# RF1_12V.net
KiCad netlist of a schematic drawn in EAGLE
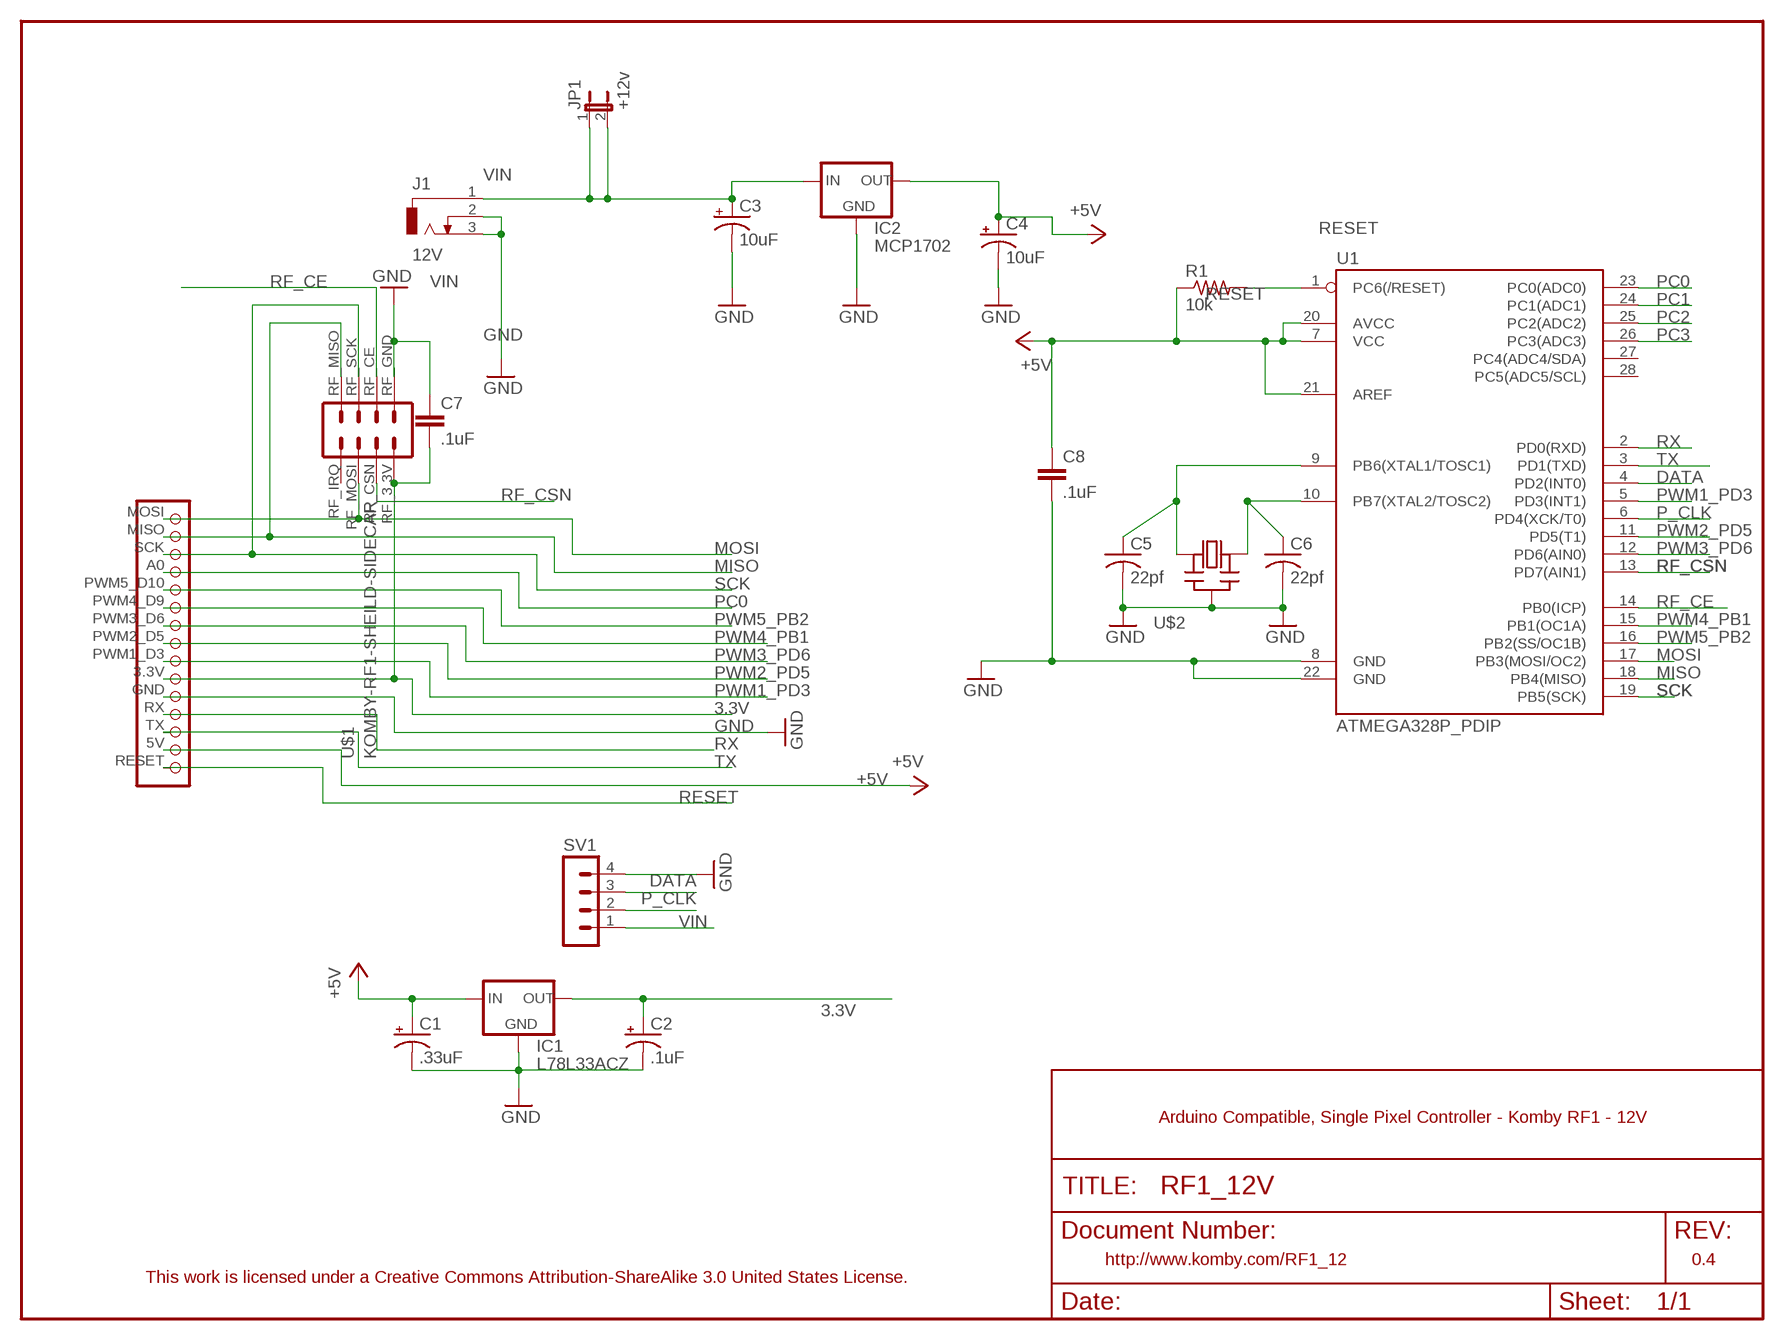
[diagram p0: schematic, sheet 1]

(export (version "E")
  (design (tool "Eeschema 10.0.6"))
  (components
    (comp (ref "C1")
      (value ".33uF")
      (footprint "eagle-import:E1,8-4")
      (libsource (lib "eagle-import") (part "CPOL-USE1.8-4"))
    )
    (comp (ref "C2")
      (value ".1uF")
      (footprint "eagle-import:E1,8-4")
      (libsource (lib "eagle-import") (part "CPOL-USE1.8-4"))
    )
    (comp (ref "C3")
      (value "10uF")
      (footprint "eagle-import:E1,8-4")
      (libsource (lib "eagle-import") (part "CPOL-USE1.8-4"))
    )
    (comp (ref "C4")
      (value "10uF")
      (footprint "eagle-import:E1,8-4")
      (libsource (lib "eagle-import") (part "CPOL-USE1.8-4"))
    )
    (comp (ref "C5")
      (value "22pf")
      (footprint "eagle-import:C0805")
      (libsource (lib "eagle-import") (part "C-USC0805"))
    )
    (comp (ref "C6")
      (value "22pf")
      (footprint "eagle-import:C0805")
      (libsource (lib "eagle-import") (part "C-USC0805"))
    )
    (comp (ref "C7")
      (value ".1uF")
      (footprint "eagle-import:C025-024X044")
      (libsource (lib "eagle-import") (part "C-EU025-024X044"))
    )
    (comp (ref "C8")
      (value ".1uF")
      (footprint "eagle-import:C025-024X044")
      (libsource (lib "eagle-import") (part "C-EU025-024X044"))
    )
    (comp (ref "IC1")
      (value "L78L33ACZ")
      (footprint "eagle-import:78LXX")
      (libsource (lib "eagle-import") (part "78LXX"))
    )
    (comp (ref "IC2")
      (value "MCP1702")
      (footprint "eagle-import:TO92")
      (libsource (lib "eagle-import") (part "MCP1700TRI"))
    )
    (comp (ref "J1")
      (value "12V")
      (footprint "eagle-import:DCJ0303")
      (libsource (lib "eagle-import") (part "DCJ0303"))
    )
    (comp (ref "JP1")
      (value "+12v")
      (footprint "eagle-import:JP1")
      (libsource (lib "eagle-import") (part "JP1E"))
    )
    (comp (ref "R1")
      (value "10k")
      (footprint "eagle-import:0207_7")
      (libsource (lib "eagle-import") (part "R-US_0207/7"))
    )
    (comp (ref "SV1")
      (value "MA04-1")
      (footprint "eagle-import:MA04-1")
      (libsource (lib "eagle-import") (part "MA04-1"))
    )
    (comp (ref "U$1")
      (value "KOMBY-RF1-SHEILD-SIDECAR")
      (footprint "eagle-import:KOMBY-RF1-SIDECAR")
      (libsource (lib "eagle-import") (part "KOMBY-RF1-SHEILD-SIDECAR"))
    )
    (comp (ref "U$2")
      (value "CERMOSCILL-THM")
      (footprint "eagle-import:CERM_OSC")
      (libsource (lib "eagle-import") (part "CERMOSCILL-THM"))
    )
    (comp (ref "U1")
      (value "ATMEGA328P_PDIP")
      (footprint "eagle-import:DIL28-3")
      (libsource (lib "eagle-import") (part "ATMEGA328P_PDIP"))
    )
  )
  (nets
    (net (code "1") (name "+5V") (class "Default")
      (node (ref "C1") (pin "+") (pinfunction "+_+") (pintype "passive"))
      (node (ref "C4") (pin "+") (pinfunction "+_+") (pintype "passive"))
      (node (ref "C8") (pin "1") (pinfunction "1_1") (pintype "passive"))
      (node (ref "IC1") (pin "IN") (pinfunction "IN_IN") (pintype "input"))
      (node (ref "IC2") (pin "3") (pinfunction "OUT_3") (pintype "passive"))
      (node (ref "R1") (pin "1") (pinfunction "1_1") (pintype "passive"))
      (node (ref "U$1") (pin "5V") (pinfunction "5V_5V") (pintype "passive"))
      (node (ref "U1") (pin "20") (pinfunction "AVCC_20") (pintype "bidirectional"))
      (node (ref "U1") (pin "21") (pinfunction "AREF_21") (pintype "bidirectional"))
      (node (ref "U1") (pin "7") (pinfunction "VCC_7") (pintype "bidirectional"))
    )
    (net (code "2") (name "/3.3V") (class "Default")
      (node (ref "C2") (pin "+") (pinfunction "+_+") (pintype "passive"))
      (node (ref "C7") (pin "2") (pinfunction "2_2") (pintype "passive"))
      (node (ref "IC1") (pin "OUT") (pinfunction "OUT_OUT") (pintype "passive"))
      (node (ref "U$1") (pin "3.3V") (pinfunction "3.3V_3.3V") (pintype "passive"))
      (node (ref "U$1") (pin "RF_3.3V") (pinfunction "RF_3.3V_RF_3.3V") (pintype "passive"))
    )
    (net (code "3") (name "/DATA") (class "Default")
      (node (ref "SV1") (pin "3") (pinfunction "3_3") (pintype "passive"))
      (node (ref "U1") (pin "4") (pinfunction "PD2(INT0)_4") (pintype "bidirectional"))
    )
    (net (code "4") (name "/MISO") (class "Default")
      (node (ref "U$1") (pin "MISO") (pinfunction "MISO_MISO") (pintype "passive"))
      (node (ref "U$1") (pin "RF_MISO") (pinfunction "RF_MISO_RF_MISO") (pintype "passive"))
      (node (ref "U1") (pin "18") (pinfunction "PB4(MISO)_18") (pintype "bidirectional"))
    )
    (net (code "5") (name "/MOSI") (class "Default")
      (node (ref "U$1") (pin "MOSI") (pinfunction "MOSI_MOSI") (pintype "passive"))
      (node (ref "U$1") (pin "RF_MOSI") (pinfunction "RF_MOSI_RF_MOSI") (pintype "passive"))
      (node (ref "U1") (pin "17") (pinfunction "PB3(MOSI/OC2)_17") (pintype "bidirectional"))
    )
    (net (code "6") (name "/PC0") (class "Default")
      (node (ref "U$1") (pin "A0") (pinfunction "PC0_A0") (pintype "passive"))
      (node (ref "U1") (pin "23") (pinfunction "PC0(ADC0)_23") (pintype "bidirectional"))
    )
    (net (code "7") (name "/PC1") (class "Default")
      (node (ref "U1") (pin "24") (pinfunction "PC1(ADC1)_24") (pintype "bidirectional"))
    )
    (net (code "8") (name "/PC2") (class "Default")
      (node (ref "U1") (pin "25") (pinfunction "PC2(ADC2)_25") (pintype "bidirectional"))
    )
    (net (code "9") (name "/PC3") (class "Default")
      (node (ref "U1") (pin "26") (pinfunction "PC3(ADC3)_26") (pintype "bidirectional"))
    )
    (net (code "10") (name "/PWM1_PD3") (class "Default")
      (node (ref "U$1") (pin "PWM1_D3") (pinfunction "PWM1_PWM1_D3") (pintype "passive"))
      (node (ref "U1") (pin "5") (pinfunction "PD3(INT1)_5") (pintype "bidirectional"))
    )
    (net (code "11") (name "/PWM2_PD5") (class "Default")
      (node (ref "U$1") (pin "PWM2_D5") (pinfunction "PWM2_PWM2_D5") (pintype "passive"))
      (node (ref "U1") (pin "11") (pinfunction "PD5(T1)_11") (pintype "bidirectional"))
    )
    (net (code "12") (name "/PWM3_PD6") (class "Default")
      (node (ref "U$1") (pin "PWM3_D6") (pinfunction "PWM3_PWM3_D6") (pintype "passive"))
      (node (ref "U1") (pin "12") (pinfunction "PD6(AIN0)_12") (pintype "bidirectional"))
    )
    (net (code "13") (name "/PWM4_PB1") (class "Default")
      (node (ref "U$1") (pin "PWM4_D9") (pinfunction "PWM4_PWM4_D9") (pintype "passive"))
      (node (ref "U1") (pin "15") (pinfunction "PB1(OC1A)_15") (pintype "bidirectional"))
    )
    (net (code "14") (name "/PWM5_PB2") (class "Default")
      (node (ref "U$1") (pin "PWM5_D10") (pinfunction "PWM5_PWM5_D10") (pintype "passive"))
      (node (ref "U1") (pin "16") (pinfunction "PB2(SS/OC1B)_16") (pintype "bidirectional"))
    )
    (net (code "15") (name "/P_CLK") (class "Default")
      (node (ref "SV1") (pin "2") (pinfunction "2_2") (pintype "passive"))
      (node (ref "U1") (pin "6") (pinfunction "PD4(XCK/T0)_6") (pintype "bidirectional"))
    )
    (net (code "16") (name "/RESET") (class "Default")
      (node (ref "R1") (pin "2") (pinfunction "2_2") (pintype "passive"))
      (node (ref "U$1") (pin "RESET") (pinfunction "RESET_RESET") (pintype "passive"))
      (node (ref "U1") (pin "1") (pinfunction "PC6(/RESET)_1") (pintype "bidirectional"))
    )
    (net (code "17") (name "/RF_CE") (class "Default")
      (node (ref "U$1") (pin "RF_CE") (pinfunction "RF_CE_RF_CE") (pintype "passive"))
      (node (ref "U1") (pin "14") (pinfunction "PB0(ICP)_14") (pintype "bidirectional"))
    )
    (net (code "18") (name "/RF_CSN") (class "Default")
      (node (ref "U$1") (pin "RF_CSN") (pinfunction "RF_CSN_RF_CSN") (pintype "passive"))
      (node (ref "U1") (pin "13") (pinfunction "PD7(AIN1)_13") (pintype "bidirectional"))
    )
    (net (code "19") (name "/RX") (class "Default")
      (node (ref "U$1") (pin "RX") (pinfunction "RX_RX") (pintype "passive"))
      (node (ref "U1") (pin "2") (pinfunction "PD0(RXD)_2") (pintype "bidirectional"))
    )
    (net (code "20") (name "/SCK") (class "Default")
      (node (ref "U$1") (pin "RF_SCK") (pinfunction "RF_SCK_RF_SCK") (pintype "passive"))
      (node (ref "U$1") (pin "SCK") (pinfunction "SCK_SCK") (pintype "passive"))
      (node (ref "U1") (pin "19") (pinfunction "PB5(SCK)_19") (pintype "bidirectional"))
    )
    (net (code "21") (name "/TX") (class "Default")
      (node (ref "U$1") (pin "TX") (pinfunction "TX_TX") (pintype "passive"))
      (node (ref "U1") (pin "3") (pinfunction "PD1(TXD)_3") (pintype "bidirectional"))
    )
    (net (code "22") (name "/VIN") (class "Default")
      (node (ref "C3") (pin "+") (pinfunction "+_+") (pintype "passive"))
      (node (ref "IC2") (pin "2") (pinfunction "IN_2") (pintype "input"))
      (node (ref "J1") (pin "1") (pinfunction "1_1") (pintype "passive"))
      (node (ref "JP1") (pin "1") (pinfunction "1_1") (pintype "passive"))
      (node (ref "JP1") (pin "2") (pinfunction "2_2") (pintype "passive"))
      (node (ref "SV1") (pin "1") (pinfunction "1_1") (pintype "passive"))
    )
    (net (code "23") (name "GND") (class "Default")
      (node (ref "C1") (pin "-") (pinfunction "-_-") (pintype "passive"))
      (node (ref "C2") (pin "-") (pinfunction "-_-") (pintype "passive"))
      (node (ref "C3") (pin "-") (pinfunction "-_-") (pintype "passive"))
      (node (ref "C4") (pin "-") (pinfunction "-_-") (pintype "passive"))
      (node (ref "C5") (pin "2") (pinfunction "2_2") (pintype "passive"))
      (node (ref "C6") (pin "2") (pinfunction "2_2") (pintype "passive"))
      (node (ref "C7") (pin "1") (pinfunction "1_1") (pintype "passive"))
      (node (ref "C8") (pin "2") (pinfunction "2_2") (pintype "passive"))
      (node (ref "IC1") (pin "GND") (pinfunction "GND_GND") (pintype "input"))
      (node (ref "IC2") (pin "1") (pinfunction "GND_1") (pintype "input"))
      (node (ref "J1") (pin "2") (pinfunction "2_2") (pintype "passive"))
      (node (ref "J1") (pin "3") (pinfunction "3_3") (pintype "passive"))
      (node (ref "SV1") (pin "4") (pinfunction "4_4") (pintype "passive"))
      (node (ref "U$1") (pin "GND") (pinfunction "GND_GND") (pintype "passive"))
      (node (ref "U$1") (pin "RF_GND") (pinfunction "RFGND_1_RF_GND") (pintype "passive"))
      (node (ref "U$2") (pin "P$2") (pinfunction "GND_P$2") (pintype "bidirectional"))
      (node (ref "U1") (pin "22") (pinfunction "GND_22") (pintype "bidirectional"))
      (node (ref "U1") (pin "8") (pinfunction "GND_8") (pintype "bidirectional"))
    )
    (net (code "24") (name "Net-(U$2-IN)") (class "Default")
      (node (ref "C5") (pin "1") (pinfunction "1_1") (pintype "passive"))
      (node (ref "U$2") (pin "P$1") (pinfunction "IN_P$1") (pintype "bidirectional"))
      (node (ref "U1") (pin "9") (pinfunction "PB6(XTAL1/TOSC1)_9") (pintype "bidirectional"))
    )
    (net (code "25") (name "Net-(U$2-OUT)") (class "Default")
      (node (ref "C6") (pin "1") (pinfunction "1_1") (pintype "passive"))
      (node (ref "U$2") (pin "P$3") (pinfunction "OUT_P$3") (pintype "bidirectional"))
      (node (ref "U1") (pin "10") (pinfunction "PB7(XTAL2/TOSC2)_10") (pintype "bidirectional"))
    )
    (net (code "26") (name "unconnected-(U$1-PadRF_IRQ)") (class "Default")
      (node (ref "U$1") (pin "RF_IRQ") (pinfunction "RF_IRQ_RF_IRQ") (pintype "passive"))
    )
    (net (code "27") (name "unconnected-(U1-PC4(ADC4{slash}SDA)-Pad27)") (class "Default")
      (node (ref "U1") (pin "27") (pinfunction "PC4(ADC4/SDA)_27") (pintype "bidirectional"))
    )
    (net (code "28") (name "unconnected-(U1-PC5(ADC5{slash}SCL)-Pad28)") (class "Default")
      (node (ref "U1") (pin "28") (pinfunction "PC5(ADC5/SCL)_28") (pintype "bidirectional"))
    )
  )
)
